# SUP_1_2_1_8.net
KiCad netlist of a schematic drawn in Altium Designer
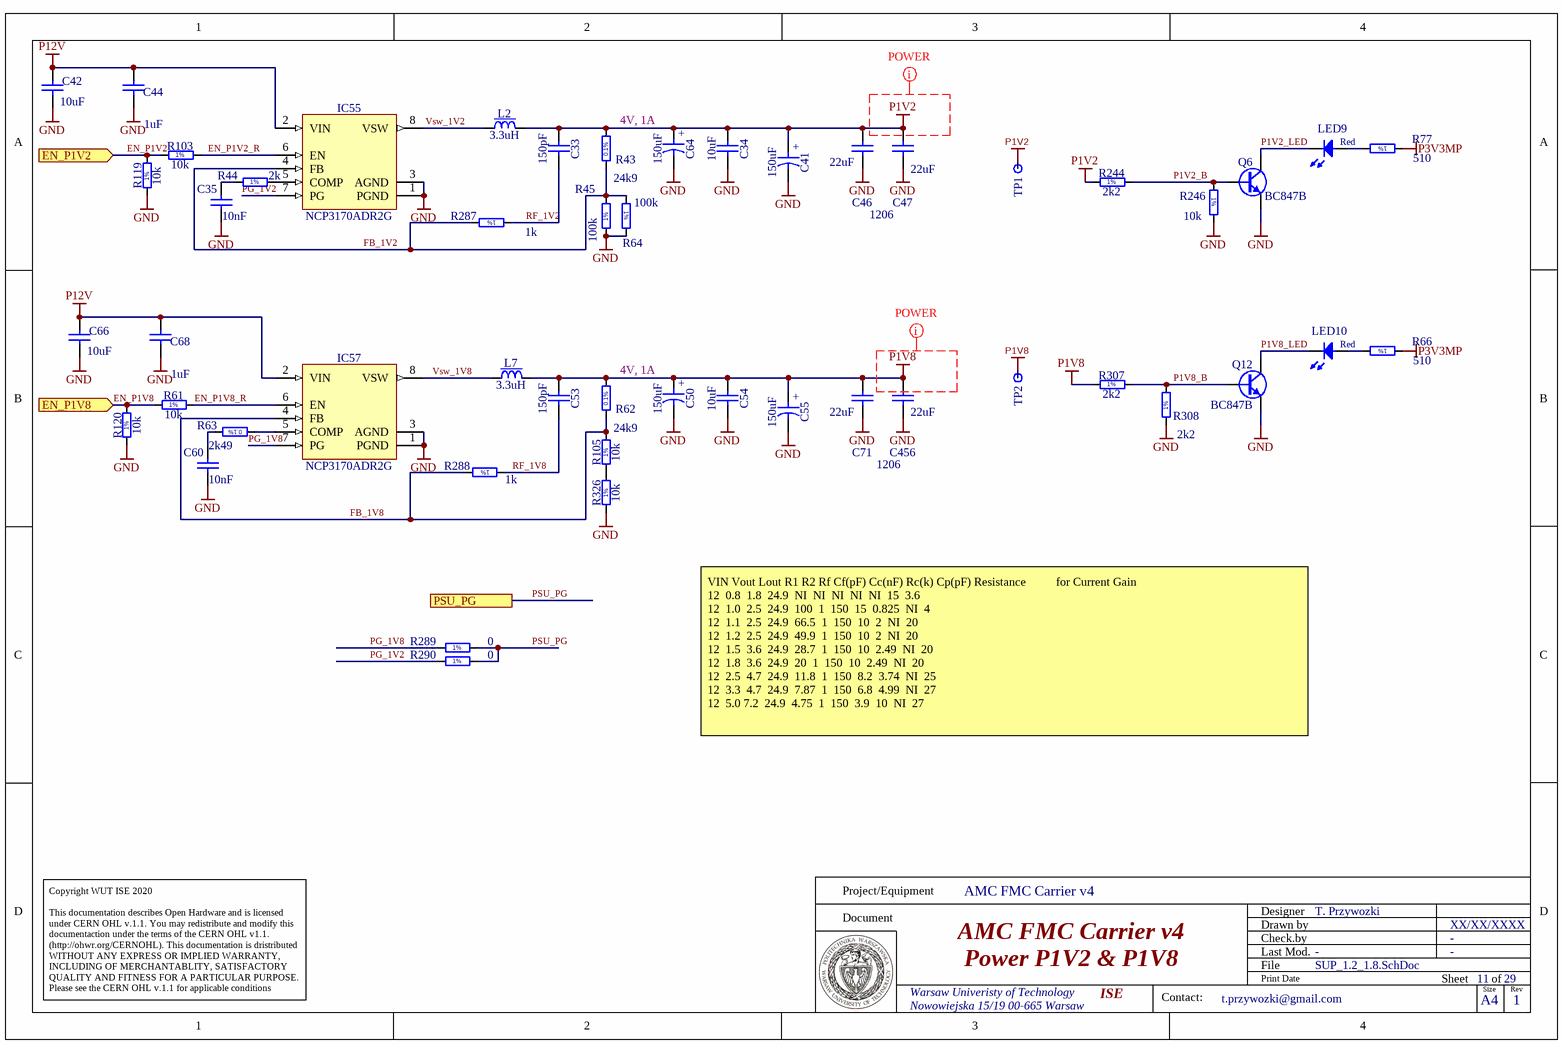
[diagram p0: SUP_1.2_1.8.SchDoc]

(export (version "E")
  (design (tool "Eeschema 10.0.6"))
  (components
    (comp (ref "C33")
      (value "150pF")
      (footprint "CAPC1608X87N")
      (description "Non-polarised capacitor")
      (fields
        (field (name "PART NUMBER") "CC0603_150PF_50V_5%_NP0")
        (field (name "VOLTAGE") "50V")
        (field (name "AUTHOR") "CERN DEM JLC")
      )
      (libsource (lib "Capacitors") (part "Capacitor - non polarized"))
    )
    (comp (ref "C34")
      (value "10uF")
      (footprint "CAPC2012X135N")
      (description "Non-polarised capacitor")
      (fields
        (field (name "PART NUMBER") "CC0805_10UF_16V_10%_X5R")
        (field (name "VOLTAGE") "16V")
        (field (name "AUTHOR") "CERN DEM JLC")
      )
      (libsource (lib "Capacitors") (part "Capacitor - non polarized"))
    )
    (comp (ref "C35")
      (value "10nF")
      (footprint "CAPC1005X55N")
      (description "Non-polarised capacitor")
      (fields
        (field (name "PART NUMBER") "CC0402_10NF_16V_10%_X7R")
        (field (name "VOLTAGE") "16V")
        (field (name "AUTHOR") "CERN DEM JLC")
      )
      (libsource (lib "Capacitors") (part "Capacitor - non polarized"))
    )
    (comp (ref "C41")
      (value "150uF")
      (footprint "CAPMP7343X200N")
      (description "Polarised capacitor")
      (fields
        (field (name "PART NUMBER") "CAEM7343-20_150UF_2V_20%_LESR0009")
        (field (name "VOLTAGE") "2V")
        (field (name "AUTHOR") "CERN DEM JLC")
      )
      (libsource (lib "Capacitors") (part "Capacitor - polarized"))
    )
    (comp (ref "C42")
      (value "10uF")
      (footprint "CAPC2012X135N")
      (description "Non-polarised capacitor")
      (fields
        (field (name "PART NUMBER") "CC0805_10UF_16V_10%_X5R")
        (field (name "VOLTAGE") "16V")
        (field (name "AUTHOR") "CERN DEM JLC")
      )
      (libsource (lib "Capacitors") (part "Capacitor - non polarized"))
    )
    (comp (ref "C44")
      (value "1uF")
      (footprint "CAPC1608X87N")
      (description "Non-polarised capacitor")
      (fields
        (field (name "PART NUMBER") "CC0603_1UF_16V_10%_X7R")
        (field (name "VOLTAGE") "16V")
        (field (name "AUTHOR") "CERN DEM JLC")
      )
      (libsource (lib "Capacitors") (part "Capacitor - non polarized"))
    )
    (comp (ref "C46")
      (value "22uF")
      (footprint "CAPC3216X180N")
      (description "Non-polarised capacitor")
      (fields
        (field (name "PART NUMBER") "CC1206_22UF_10V_10%_X7R")
        (field (name "VOLTAGE") "10V")
        (field (name "AUTHOR") "CERN DEM JLC")
      )
      (libsource (lib "Capacitors") (part "Capacitor - non polarized"))
    )
    (comp (ref "C47")
      (value "22uF")
      (footprint "CAPC3216X180N")
      (description "Non-polarised capacitor")
      (fields
        (field (name "PART NUMBER") "CC1206_22UF_10V_10%_X7R")
        (field (name "VOLTAGE") "10V")
        (field (name "CASE") "1206")
        (field (name "AUTHOR") "CERN DEM JLC")
      )
      (libsource (lib "Capacitors") (part "Capacitor - non polarized"))
    )
    (comp (ref "C50")
      (value "150uF")
      (footprint "CAPMP7343X200N")
      (description "Polarised capacitor")
      (fields
        (field (name "PART NUMBER") "CAEM7343-20_150UF_2V_20%_LESR0009")
        (field (name "VOLTAGE") "2V")
        (field (name "AUTHOR") "CERN DEM JLC")
      )
      (libsource (lib "Capacitors") (part "Capacitor - polarized"))
    )
    (comp (ref "C53")
      (value "150pF")
      (footprint "CAPC1608X87N")
      (description "Non-polarised capacitor")
      (fields
        (field (name "PART NUMBER") "CC0603_150PF_50V_5%_NP0")
        (field (name "VOLTAGE") "50V")
        (field (name "AUTHOR") "CERN DEM JLC")
      )
      (libsource (lib "Capacitors") (part "Capacitor - non polarized"))
    )
    (comp (ref "C54")
      (value "10uF")
      (footprint "CAPC2012X135N")
      (description "Non-polarised capacitor")
      (fields
        (field (name "PART NUMBER") "CC0805_10UF_16V_10%_X5R")
        (field (name "VOLTAGE") "16V")
        (field (name "AUTHOR") "CERN DEM JLC")
      )
      (libsource (lib "Capacitors") (part "Capacitor - non polarized"))
    )
    (comp (ref "C55")
      (value "150uF")
      (footprint "CAPMP7343X200N")
      (description "Polarised capacitor")
      (fields
        (field (name "PART NUMBER") "CAEM7343-20_150UF_2V_20%_LESR0009")
        (field (name "VOLTAGE") "2V")
        (field (name "AUTHOR") "CERN DEM JLC")
      )
      (libsource (lib "Capacitors") (part "Capacitor - polarized"))
    )
    (comp (ref "C60")
      (value "10nF")
      (footprint "CAPC1005X55N")
      (description "Non-polarised capacitor")
      (fields
        (field (name "PART NUMBER") "CC0402_10NF_16V_10%_X7R")
        (field (name "VOLTAGE") "16V")
        (field (name "AUTHOR") "CERN DEM JLC")
      )
      (libsource (lib "Capacitors") (part "Capacitor - non polarized"))
    )
    (comp (ref "C64")
      (value "150uF")
      (footprint "CAPMP7343X200N")
      (description "Polarised capacitor")
      (fields
        (field (name "PART NUMBER") "CAEM7343-20_150UF_2V_20%_LESR0009")
        (field (name "VOLTAGE") "2V")
        (field (name "AUTHOR") "CERN DEM JLC")
      )
      (libsource (lib "Capacitors") (part "Capacitor - polarized"))
    )
    (comp (ref "C66")
      (value "10uF")
      (footprint "CAPC2012X135N")
      (description "Non-polarised capacitor")
      (fields
        (field (name "PART NUMBER") "CC0805_10UF_16V_10%_X5R")
        (field (name "VOLTAGE") "16V")
        (field (name "AUTHOR") "CERN DEM JLC")
      )
      (libsource (lib "Capacitors") (part "Capacitor - non polarized"))
    )
    (comp (ref "C68")
      (value "1uF")
      (footprint "CAPC1608X87N")
      (description "Non-polarised capacitor")
      (fields
        (field (name "PART NUMBER") "CC0603_1UF_16V_10%_X7R")
        (field (name "VOLTAGE") "16V")
        (field (name "AUTHOR") "CERN DEM JLC")
      )
      (libsource (lib "Capacitors") (part "Capacitor - non polarized"))
    )
    (comp (ref "C71")
      (value "22uF")
      (footprint "CAPC3216X180N")
      (description "Non-polarised capacitor")
      (fields
        (field (name "PART NUMBER") "CC1206_22UF_10V_10%_X7R")
        (field (name "VOLTAGE") "10V")
        (field (name "AUTHOR") "CERN DEM JLC")
      )
      (libsource (lib "Capacitors") (part "Capacitor - non polarized"))
    )
    (comp (ref "C456")
      (value "22uF")
      (footprint "CAPC3216X180N")
      (description "Non-polarised capacitor")
      (fields
        (field (name "PART NUMBER") "CC1206_22UF_10V_10%_X7R")
        (field (name "VOLTAGE") "10V")
        (field (name "CASE") "1206")
        (field (name "AUTHOR") "CERN DEM JLC")
      )
      (libsource (lib "Capacitors") (part "Capacitor - non polarized"))
    )
    (comp (ref "IC55")
      (value "NCP3170ADR2G")
      (footprint "SOIC127P600X175-8N")
      (description "Synchronous PWM Switching Converter")
      (fields (field (name "MANUFACTURER") "ON SEMICONDUCTOR") (field (name "AUTHOR") "CERN DEM MR"))
      (libsource (lib "ICs And Semiconductors") (part "NCP3170ADR2G"))
    )
    (comp (ref "IC57")
      (value "NCP3170ADR2G")
      (footprint "SOIC127P600X175-8N")
      (description "Synchronous PWM Switching Converter")
      (fields (field (name "MANUFACTURER") "ON SEMICONDUCTOR") (field (name "AUTHOR") "CERN DEM MR"))
      (libsource (lib "ICs And Semiconductors") (part "NCP3170ADR2G"))
    )
    (comp (ref "L2")
      (value "3.3uH")
      (footprint "IND_WURTH_WE-PD4_L")
      (description "Inductor With Core")
      (fields
        (field (name "PART NUMBER") "IND_3.3UH_20%_WURTH_WE-PD4_74456033")
        (field (name "POWER") "5.3A")
        (field (name "AUTHOR") "CERN DEM JLC")
      )
      (libsource (lib "Inductors & Transformers") (part "Inductor With Magnetic core"))
    )
    (comp (ref "L7")
      (value "3.3uH")
      (footprint "IND_WURTH_WE-PD4_L")
      (description "Inductor With Core")
      (fields
        (field (name "PART NUMBER") "IND_3.3UH_20%_WURTH_WE-PD4_74456033")
        (field (name "POWER") "5.3A")
        (field (name "AUTHOR") "CERN DEM JLC")
      )
      (libsource (lib "Inductors & Transformers") (part "Inductor With Magnetic core"))
    )
    (comp (ref "LED9")
      (value "Red")
      (footprint "LED_KINGBRIGHT_KPH-1608SURCK")
      (description "LED Red 1C 2A")
      (fields
        (field (name "PART NUMBER") "LED_KINGBRIGHT_KPH-1608SURCK")
        (field (name "MANUFACTURER") "KINGBRIGHT")
        (field (name "AUTHOR") "CERN DEM JLC")
      )
      (libsource (lib "ICs And Semiconductors") (part "LED Red 1C 2A"))
    )
    (comp (ref "LED10")
      (value "Red")
      (footprint "LED_KINGBRIGHT_KPH-1608SURCK")
      (description "LED Red 1C 2A")
      (fields
        (field (name "PART NUMBER") "LED_KINGBRIGHT_KPH-1608SURCK")
        (field (name "MANUFACTURER") "KINGBRIGHT")
        (field (name "AUTHOR") "CERN DEM JLC")
      )
      (libsource (lib "ICs And Semiconductors") (part "LED Red 1C 2A"))
    )
    (comp (ref "Q6")
      (value "BC847B")
      (footprint "SOT95P230X110-3N")
      (description "NPN Transistor")
      (fields (field (name "MANUFACTURER") "NXP SEMICONDUCTORS") (field (name "AUTHOR") "CERN DEM JLC"))
      (libsource (lib "ICs And Semiconductors") (part "NPN B1 E2 C3"))
    )
    (comp (ref "Q12")
      (value "BC847B")
      (footprint "SOT95P230X110-3N")
      (description "NPN Transistor")
      (fields (field (name "MANUFACTURER") "NXP SEMICONDUCTORS") (field (name "AUTHOR") "CERN DEM JLC"))
      (libsource (lib "ICs And Semiconductors") (part "NPN B1 E2 C3"))
    )
    (comp (ref "R43")
      (value "24k9")
      (footprint "RESC1608X55N")
      (description "Resistor - 0.1%")
      (fields
        (field (name "PART NUMBER") "R0603_24K9_0.1%_0.063W_10PPM")
        (field (name "POWER") "0.063W")
        (field (name "AUTHOR") "CERN DEM JLC")
      )
      (libsource (lib "Resistors") (part "Resistor - 0.1%"))
    )
    (comp (ref "R44")
      (value "2k")
      (footprint "RESC1608X55N")
      (description "Resistor - 1%")
      (fields
        (field (name "PART NUMBER") "R0603_2K_1%_0.1W_100PPM")
        (field (name "POWER") "0.1W")
        (field (name "AUTHOR") "CERN DEM JLC")
      )
      (libsource (lib "Resistors") (part "Resistor - 1%"))
    )
    (comp (ref "R45")
      (value "100k")
      (footprint "RESC1005X40N")
      (description "Resistor - 1%")
      (fields
        (field (name "PART NUMBER") "R0402_100K_1%_0.0625W_100PPM")
        (field (name "POWER") "0.0625W")
        (field (name "AUTHOR") "CERN DEM JLC")
      )
      (libsource (lib "Resistors") (part "Resistor - 1%"))
    )
    (comp (ref "R61")
      (value "10k")
      (footprint "RESC1005X40N")
      (description "Resistor - 1%")
      (fields
        (field (name "PART NUMBER") "R0402_10K_1%_0.0625W_100PPM")
        (field (name "POWER") "0.0625W")
        (field (name "AUTHOR") "CERN DEM JLC")
      )
      (libsource (lib "Resistors") (part "Resistor - 1%"))
    )
    (comp (ref "R62")
      (value "24k9")
      (footprint "RESC1608X55N")
      (description "Resistor - 0.1%")
      (fields
        (field (name "PART NUMBER") "R0603_24K9_0.1%_0.063W_10PPM")
        (field (name "POWER") "0.063W")
        (field (name "AUTHOR") "CERN DEM JLC")
      )
      (libsource (lib "Resistors") (part "Resistor - 0.1%"))
    )
    (comp (ref "R63")
      (value "2k49")
      (footprint "RESC1608X55N")
      (description "Resistor - 0.1%")
      (fields
        (field (name "PART NUMBER") "R0603_2K49_0.1%_0.063W_10PPM")
        (field (name "POWER") "0.063W")
        (field (name "AUTHOR") "CERN DEM JLC")
      )
      (libsource (lib "Resistors") (part "Resistor - 0.1%"))
    )
    (comp (ref "R64")
      (value "100k")
      (footprint "RESC1005X40N")
      (description "Resistor - 1%")
      (fields
        (field (name "PART NUMBER") "R0402_100K_1%_0.0625W_100PPM")
        (field (name "POWER") "0.0625W")
        (field (name "AUTHOR") "CERN DEM JLC")
      )
      (libsource (lib "Resistors") (part "Resistor - 1%"))
    )
    (comp (ref "R66")
      (value "510")
      (footprint "RESC1005X40N")
      (description "Resistor - 1%")
      (fields
        (field (name "PART NUMBER") "R0402_510R_1%_0.0625W_100PPM")
        (field (name "POWER") "0.0625W")
        (field (name "AUTHOR") "CERN DEM JLC")
      )
      (libsource (lib "Resistors") (part "Resistor - 1%"))
    )
    (comp (ref "R77")
      (value "510")
      (footprint "RESC1005X40N")
      (description "Resistor - 1%")
      (fields
        (field (name "PART NUMBER") "R0402_510R_1%_0.0625W_100PPM")
        (field (name "POWER") "0.0625W")
        (field (name "AUTHOR") "CERN DEM JLC")
      )
      (libsource (lib "Resistors") (part "Resistor - 1%"))
    )
    (comp (ref "R103")
      (value "10k")
      (footprint "RESC1005X40N")
      (description "Resistor - 1%")
      (fields
        (field (name "PART NUMBER") "R0402_10K_1%_0.0625W_100PPM")
        (field (name "POWER") "0.0625W")
        (field (name "AUTHOR") "CERN DEM JLC")
      )
      (libsource (lib "Resistors") (part "Resistor - 1%"))
    )
    (comp (ref "R105")
      (value "10k")
      (footprint "RESC1005X40N")
      (description "Resistor - 1%")
      (fields
        (field (name "PART NUMBER") "R0402_10K_1%_0.0625W_100PPM")
        (field (name "POWER") "0.0625W")
        (field (name "AUTHOR") "CERN DEM JLC")
      )
      (libsource (lib "Resistors") (part "Resistor - 1%"))
    )
    (comp (ref "R119")
      (value "10k")
      (footprint "RESC1005X40N")
      (description "Resistor - 1%")
      (fields
        (field (name "PART NUMBER") "R0402_10K_1%_0.0625W_100PPM")
        (field (name "POWER") "0.0625W")
        (field (name "AUTHOR") "CERN DEM JLC")
      )
      (libsource (lib "Resistors") (part "Resistor - 1%"))
    )
    (comp (ref "R120")
      (value "10k")
      (footprint "RESC1005X40N")
      (description "Resistor - 1%")
      (fields
        (field (name "PART NUMBER") "R0402_10K_1%_0.0625W_100PPM")
        (field (name "POWER") "0.0625W")
        (field (name "AUTHOR") "CERN DEM JLC")
      )
      (libsource (lib "Resistors") (part "Resistor - 1%"))
    )
    (comp (ref "R244")
      (value "2k2")
      (footprint "RESC1005X40N")
      (description "Resistor - 1%")
      (fields
        (field (name "PART NUMBER") "R0402_2K2_1%_0.0625W_100PPM")
        (field (name "POWER") "0.0625W")
        (field (name "AUTHOR") "CERN DEM JLC")
      )
      (libsource (lib "Resistors") (part "Resistor - 1%"))
    )
    (comp (ref "R246")
      (value "10k")
      (footprint "RESC1005X40N")
      (description "Resistor - 1%")
      (fields
        (field (name "PART NUMBER") "R0402_10K_1%_0.0625W_100PPM")
        (field (name "POWER") "0.0625W")
        (field (name "AUTHOR") "CERN DEM JLC")
      )
      (libsource (lib "Resistors") (part "Resistor - 1%"))
    )
    (comp (ref "R287")
      (value "1k")
      (footprint "RESC1005X40N")
      (description "Resistor - 1%")
      (fields
        (field (name "PART NUMBER") "R0402_1K_1%_0.0625W_100PPM")
        (field (name "POWER") "0.0625W")
        (field (name "AUTHOR") "CERN DEM JLC")
      )
      (libsource (lib "Resistors") (part "Resistor - 1%"))
    )
    (comp (ref "R288")
      (value "1k")
      (footprint "RESC1005X40N")
      (description "Resistor - 1%")
      (fields
        (field (name "PART NUMBER") "R0402_1K_1%_0.0625W_100PPM")
        (field (name "POWER") "0.0625W")
        (field (name "AUTHOR") "CERN DEM JLC")
      )
      (libsource (lib "Resistors") (part "Resistor - 1%"))
    )
    (comp (ref "R289")
      (value "0")
      (footprint "RESC1005X40N")
      (description "Resistor - 1%")
      (fields
        (field (name "PART NUMBER") "R0402_0R_JUMPER")
        (field (name "MANUFACTURER") "GENERIC")
        (field (name "AUTHOR") "CERN DEM JLC")
      )
      (libsource (lib "Resistors") (part "Resistor - 1%"))
    )
    (comp (ref "R290")
      (value "0")
      (footprint "RESC1005X40N")
      (description "Resistor - 1%")
      (fields
        (field (name "PART NUMBER") "R0402_0R_JUMPER")
        (field (name "MANUFACTURER") "GENERIC")
        (field (name "AUTHOR") "CERN DEM JLC")
      )
      (libsource (lib "Resistors") (part "Resistor - 1%"))
    )
    (comp (ref "R307")
      (value "2k2")
      (footprint "RESC1005X40N")
      (description "Resistor - 1%")
      (fields
        (field (name "PART NUMBER") "R0402_2K2_1%_0.0625W_100PPM")
        (field (name "POWER") "0.0625W")
        (field (name "AUTHOR") "CERN DEM JLC")
      )
      (libsource (lib "Resistors") (part "Resistor - 1%"))
    )
    (comp (ref "R308")
      (value "2k2")
      (footprint "RESC1005X40N")
      (description "Resistor - 1%")
      (fields
        (field (name "PART NUMBER") "R0402_2K2_1%_0.0625W_100PPM")
        (field (name "POWER") "0.0625W")
        (field (name "AUTHOR") "CERN DEM JLC")
      )
      (libsource (lib "Resistors") (part "Resistor - 1%"))
    )
    (comp (ref "R326")
      (value "10k")
      (footprint "RESC1005X40N")
      (description "Resistor - 1%")
      (fields
        (field (name "PART NUMBER") "R0402_10K_1%_0.0625W_100PPM")
        (field (name "POWER") "0.0625W")
        (field (name "AUTHOR") "CERN DEM JLC")
      )
      (libsource (lib "Resistors") (part "Resistor - 1%"))
    )
    (comp (ref "TP1")
      (value "Test Point")
      (footprint "TPS127")
      (fields (field (name "PART NUMBER") "SMD_PAD_1.27X1.27MM") (field (name "AUTHOR") "CERN DEM JLC"))
      (libsource (lib "Eletro-mechanical") (part "Test Point"))
    )
    (comp (ref "TP2")
      (value "Test Point")
      (footprint "TPS127")
      (fields (field (name "PART NUMBER") "SMD_PAD_1.27X1.27MM") (field (name "AUTHOR") "CERN DEM JLC"))
      (libsource (lib "Eletro-mechanical") (part "Test Point"))
    )
  )
  (nets
    (net (code "1") (name "/EN_P1V2") (class "Default")
      (node (ref "R103") (pin "1") (pinfunction "1_1") (pintype "passive"))
      (node (ref "R119") (pin "2") (pinfunction "2_2") (pintype "passive"))
    )
    (net (code "2") (name "/EN_P1V2_R") (class "Default")
      (node (ref "IC55") (pin "6") (pinfunction "EN_6") (pintype "input"))
      (node (ref "R103") (pin "2") (pinfunction "2_2") (pintype "passive"))
    )
    (net (code "3") (name "/EN_P1V8") (class "Default")
      (node (ref "R120") (pin "2") (pinfunction "2_2") (pintype "passive"))
      (node (ref "R61") (pin "1") (pinfunction "1_1") (pintype "passive"))
    )
    (net (code "4") (name "/EN_P1V8_R") (class "Default")
      (node (ref "IC57") (pin "6") (pinfunction "EN_6") (pintype "input"))
      (node (ref "R61") (pin "2") (pinfunction "2_2") (pintype "passive"))
    )
    (net (code "5") (name "/FB_1V2") (class "Default")
      (node (ref "IC55") (pin "4") (pinfunction "FB_4") (pintype "input"))
      (node (ref "R287") (pin "2") (pinfunction "2_2") (pintype "passive"))
      (node (ref "R43") (pin "1") (pinfunction "1_1") (pintype "passive"))
      (node (ref "R45") (pin "2") (pinfunction "2_2") (pintype "passive"))
      (node (ref "R64") (pin "1") (pinfunction "1_1") (pintype "passive"))
    )
    (net (code "6") (name "/FB_1V8") (class "Default")
      (node (ref "IC57") (pin "4") (pinfunction "FB_4") (pintype "input"))
      (node (ref "R105") (pin "2") (pinfunction "2_2") (pintype "passive"))
      (node (ref "R288") (pin "2") (pinfunction "2_2") (pintype "passive"))
      (node (ref "R62") (pin "1") (pinfunction "1_1") (pintype "passive"))
    )
    (net (code "7") (name "/P1V2_B") (class "Default")
      (node (ref "Q6") (pin "1") (pinfunction "B_1") (pintype "passive"))
      (node (ref "R244") (pin "2") (pinfunction "2_2") (pintype "passive"))
      (node (ref "R246") (pin "1") (pinfunction "1_1") (pintype "passive"))
    )
    (net (code "8") (name "/P1V2_LED") (class "Default")
      (node (ref "LED9") (pin "1") (pinfunction "C_1") (pintype "passive"))
      (node (ref "Q6") (pin "3") (pinfunction "C_3") (pintype "passive"))
    )
    (net (code "9") (name "/P1V8_B") (class "Default")
      (node (ref "Q12") (pin "1") (pinfunction "B_1") (pintype "passive"))
      (node (ref "R307") (pin "2") (pinfunction "2_2") (pintype "passive"))
      (node (ref "R308") (pin "2") (pinfunction "2_2") (pintype "passive"))
    )
    (net (code "10") (name "/P1V8_LED") (class "Default")
      (node (ref "LED10") (pin "1") (pinfunction "C_1") (pintype "passive"))
      (node (ref "Q12") (pin "3") (pinfunction "C_3") (pintype "passive"))
    )
    (net (code "11") (name "/PG_1V2") (class "Default")
      (node (ref "IC55") (pin "7") (pinfunction "PG_7") (pintype "input"))
      (node (ref "R290") (pin "2") (pinfunction "2_2") (pintype "passive"))
    )
    (net (code "12") (name "/PG_1V8") (class "Default")
      (node (ref "IC57") (pin "7") (pinfunction "PG_7") (pintype "input"))
      (node (ref "R289") (pin "2") (pinfunction "2_2") (pintype "passive"))
    )
    (net (code "13") (name "/PSU_PG") (class "Default")
      (node (ref "R289") (pin "1") (pinfunction "1_1") (pintype "passive"))
      (node (ref "R290") (pin "1") (pinfunction "1_1") (pintype "passive"))
    )
    (net (code "14") (name "/RF_1V2") (class "Default")
      (node (ref "C33") (pin "2") (pinfunction "2_2") (pintype "passive"))
      (node (ref "R287") (pin "1") (pinfunction "1_1") (pintype "passive"))
    )
    (net (code "15") (name "/RF_1V8") (class "Default")
      (node (ref "C53") (pin "2") (pinfunction "2_2") (pintype "passive"))
      (node (ref "R288") (pin "1") (pinfunction "1_1") (pintype "passive"))
    )
    (net (code "16") (name "/Vsw_1V2") (class "Default")
      (node (ref "IC55") (pin "8") (pinfunction "VSW_8") (pintype "output"))
      (node (ref "L2") (pin "1") (pinfunction "1_1") (pintype "passive"))
    )
    (net (code "17") (name "/Vsw_1V8") (class "Default")
      (node (ref "IC57") (pin "8") (pinfunction "VSW_8") (pintype "output"))
      (node (ref "L7") (pin "1") (pinfunction "1_1") (pintype "passive"))
    )
    (net (code "18") (name "GND") (class "Default")
      (node (ref "C34") (pin "2") (pinfunction "2_2") (pintype "passive"))
      (node (ref "C35") (pin "2") (pinfunction "2_2") (pintype "passive"))
      (node (ref "C41") (pin "2") (pinfunction "2_2") (pintype "passive"))
      (node (ref "C42") (pin "1") (pinfunction "1_1") (pintype "passive"))
      (node (ref "C44") (pin "1") (pinfunction "1_1") (pintype "passive"))
      (node (ref "C456") (pin "2") (pinfunction "2_2") (pintype "passive"))
      (node (ref "C46") (pin "2") (pinfunction "2_2") (pintype "passive"))
      (node (ref "C47") (pin "2") (pinfunction "2_2") (pintype "passive"))
      (node (ref "C50") (pin "2") (pinfunction "2_2") (pintype "passive"))
      (node (ref "C54") (pin "2") (pinfunction "2_2") (pintype "passive"))
      (node (ref "C55") (pin "2") (pinfunction "2_2") (pintype "passive"))
      (node (ref "C60") (pin "1") (pinfunction "1_1") (pintype "passive"))
      (node (ref "C64") (pin "2") (pinfunction "2_2") (pintype "passive"))
      (node (ref "C66") (pin "1") (pinfunction "1_1") (pintype "passive"))
      (node (ref "C68") (pin "1") (pinfunction "1_1") (pintype "passive"))
      (node (ref "C71") (pin "2") (pinfunction "2_2") (pintype "passive"))
      (node (ref "IC55") (pin "1") (pinfunction "PGND_1") (pintype "power_in"))
      (node (ref "IC55") (pin "3") (pinfunction "AGND_3") (pintype "power_in"))
      (node (ref "IC57") (pin "1") (pinfunction "PGND_1") (pintype "power_in"))
      (node (ref "IC57") (pin "3") (pinfunction "AGND_3") (pintype "power_in"))
      (node (ref "Q12") (pin "2") (pinfunction "E_2") (pintype "passive"))
      (node (ref "Q6") (pin "2") (pinfunction "E_2") (pintype "passive"))
      (node (ref "R119") (pin "1") (pinfunction "1_1") (pintype "passive"))
      (node (ref "R120") (pin "1") (pinfunction "1_1") (pintype "passive"))
      (node (ref "R246") (pin "2") (pinfunction "2_2") (pintype "passive"))
      (node (ref "R308") (pin "1") (pinfunction "1_1") (pintype "passive"))
      (node (ref "R326") (pin "1") (pinfunction "1_1") (pintype "passive"))
      (node (ref "R45") (pin "1") (pinfunction "1_1") (pintype "passive"))
      (node (ref "R64") (pin "2") (pinfunction "2_2") (pintype "passive"))
    )
    (net (code "19") (name "Net-(C35-Pad1)") (class "Default")
      (node (ref "C35") (pin "1") (pinfunction "1_1") (pintype "passive"))
      (node (ref "R44") (pin "2") (pinfunction "2_2") (pintype "passive"))
    )
    (net (code "20") (name "Net-(C60-Pad2)") (class "Default")
      (node (ref "C60") (pin "2") (pinfunction "2_2") (pintype "passive"))
      (node (ref "R63") (pin "1") (pinfunction "1_1") (pintype "passive"))
    )
    (net (code "21") (name "Net-(IC55-COMP)") (class "Default")
      (node (ref "IC55") (pin "5") (pinfunction "COMP_5") (pintype "input"))
      (node (ref "R44") (pin "1") (pinfunction "1_1") (pintype "passive"))
    )
    (net (code "22") (name "Net-(IC57-COMP)") (class "Default")
      (node (ref "IC57") (pin "5") (pinfunction "COMP_5") (pintype "input"))
      (node (ref "R63") (pin "2") (pinfunction "2_2") (pintype "passive"))
    )
    (net (code "23") (name "Net-(LED9-A)") (class "Default")
      (node (ref "LED9") (pin "2") (pinfunction "A_2") (pintype "passive"))
      (node (ref "R77") (pin "2") (pinfunction "2_2") (pintype "passive"))
    )
    (net (code "24") (name "Net-(LED10-A)") (class "Default")
      (node (ref "LED10") (pin "2") (pinfunction "A_2") (pintype "passive"))
      (node (ref "R66") (pin "2") (pinfunction "2_2") (pintype "passive"))
    )
    (net (code "25") (name "Net-(R105-Pad1)") (class "Default")
      (node (ref "R105") (pin "1") (pinfunction "1_1") (pintype "passive"))
      (node (ref "R326") (pin "2") (pinfunction "2_2") (pintype "passive"))
    )
    (net (code "26") (name "P1V2") (class "Default")
      (node (ref "C33") (pin "1") (pinfunction "1_1") (pintype "passive"))
      (node (ref "C34") (pin "1") (pinfunction "1_1") (pintype "passive"))
      (node (ref "C41") (pin "1") (pinfunction "1_1") (pintype "passive"))
      (node (ref "C46") (pin "1") (pinfunction "1_1") (pintype "passive"))
      (node (ref "C47") (pin "1") (pinfunction "1_1") (pintype "passive"))
      (node (ref "C64") (pin "1") (pinfunction "1_1") (pintype "passive"))
      (node (ref "L2") (pin "2") (pinfunction "2_2") (pintype "passive"))
      (node (ref "R244") (pin "1") (pinfunction "1_1") (pintype "passive"))
      (node (ref "R43") (pin "2") (pinfunction "2_2") (pintype "passive"))
      (node (ref "TP1") (pin "1") (pinfunction "1_1") (pintype "bidirectional"))
    )
    (net (code "27") (name "P1V8") (class "Default")
      (node (ref "C456") (pin "1") (pinfunction "1_1") (pintype "passive"))
      (node (ref "C50") (pin "1") (pinfunction "1_1") (pintype "passive"))
      (node (ref "C53") (pin "1") (pinfunction "1_1") (pintype "passive"))
      (node (ref "C54") (pin "1") (pinfunction "1_1") (pintype "passive"))
      (node (ref "C55") (pin "1") (pinfunction "1_1") (pintype "passive"))
      (node (ref "C71") (pin "1") (pinfunction "1_1") (pintype "passive"))
      (node (ref "L7") (pin "2") (pinfunction "2_2") (pintype "passive"))
      (node (ref "R307") (pin "1") (pinfunction "1_1") (pintype "passive"))
      (node (ref "R62") (pin "2") (pinfunction "2_2") (pintype "passive"))
      (node (ref "TP2") (pin "1") (pinfunction "1_1") (pintype "bidirectional"))
    )
    (net (code "28") (name "P3V3MP") (class "Default")
      (node (ref "R66") (pin "1") (pinfunction "1_1") (pintype "passive"))
      (node (ref "R77") (pin "1") (pinfunction "1_1") (pintype "passive"))
    )
    (net (code "29") (name "P12V") (class "Default")
      (node (ref "C42") (pin "2") (pinfunction "2_2") (pintype "passive"))
      (node (ref "C44") (pin "2") (pinfunction "2_2") (pintype "passive"))
      (node (ref "C66") (pin "2") (pinfunction "2_2") (pintype "passive"))
      (node (ref "C68") (pin "2") (pinfunction "2_2") (pintype "passive"))
      (node (ref "IC55") (pin "2") (pinfunction "VIN_2") (pintype "input"))
      (node (ref "IC57") (pin "2") (pinfunction "VIN_2") (pintype "input"))
    )
  )
)
